# mimic1567heatSink.net
KiCad netlist of a schematic drawn in EAGLE
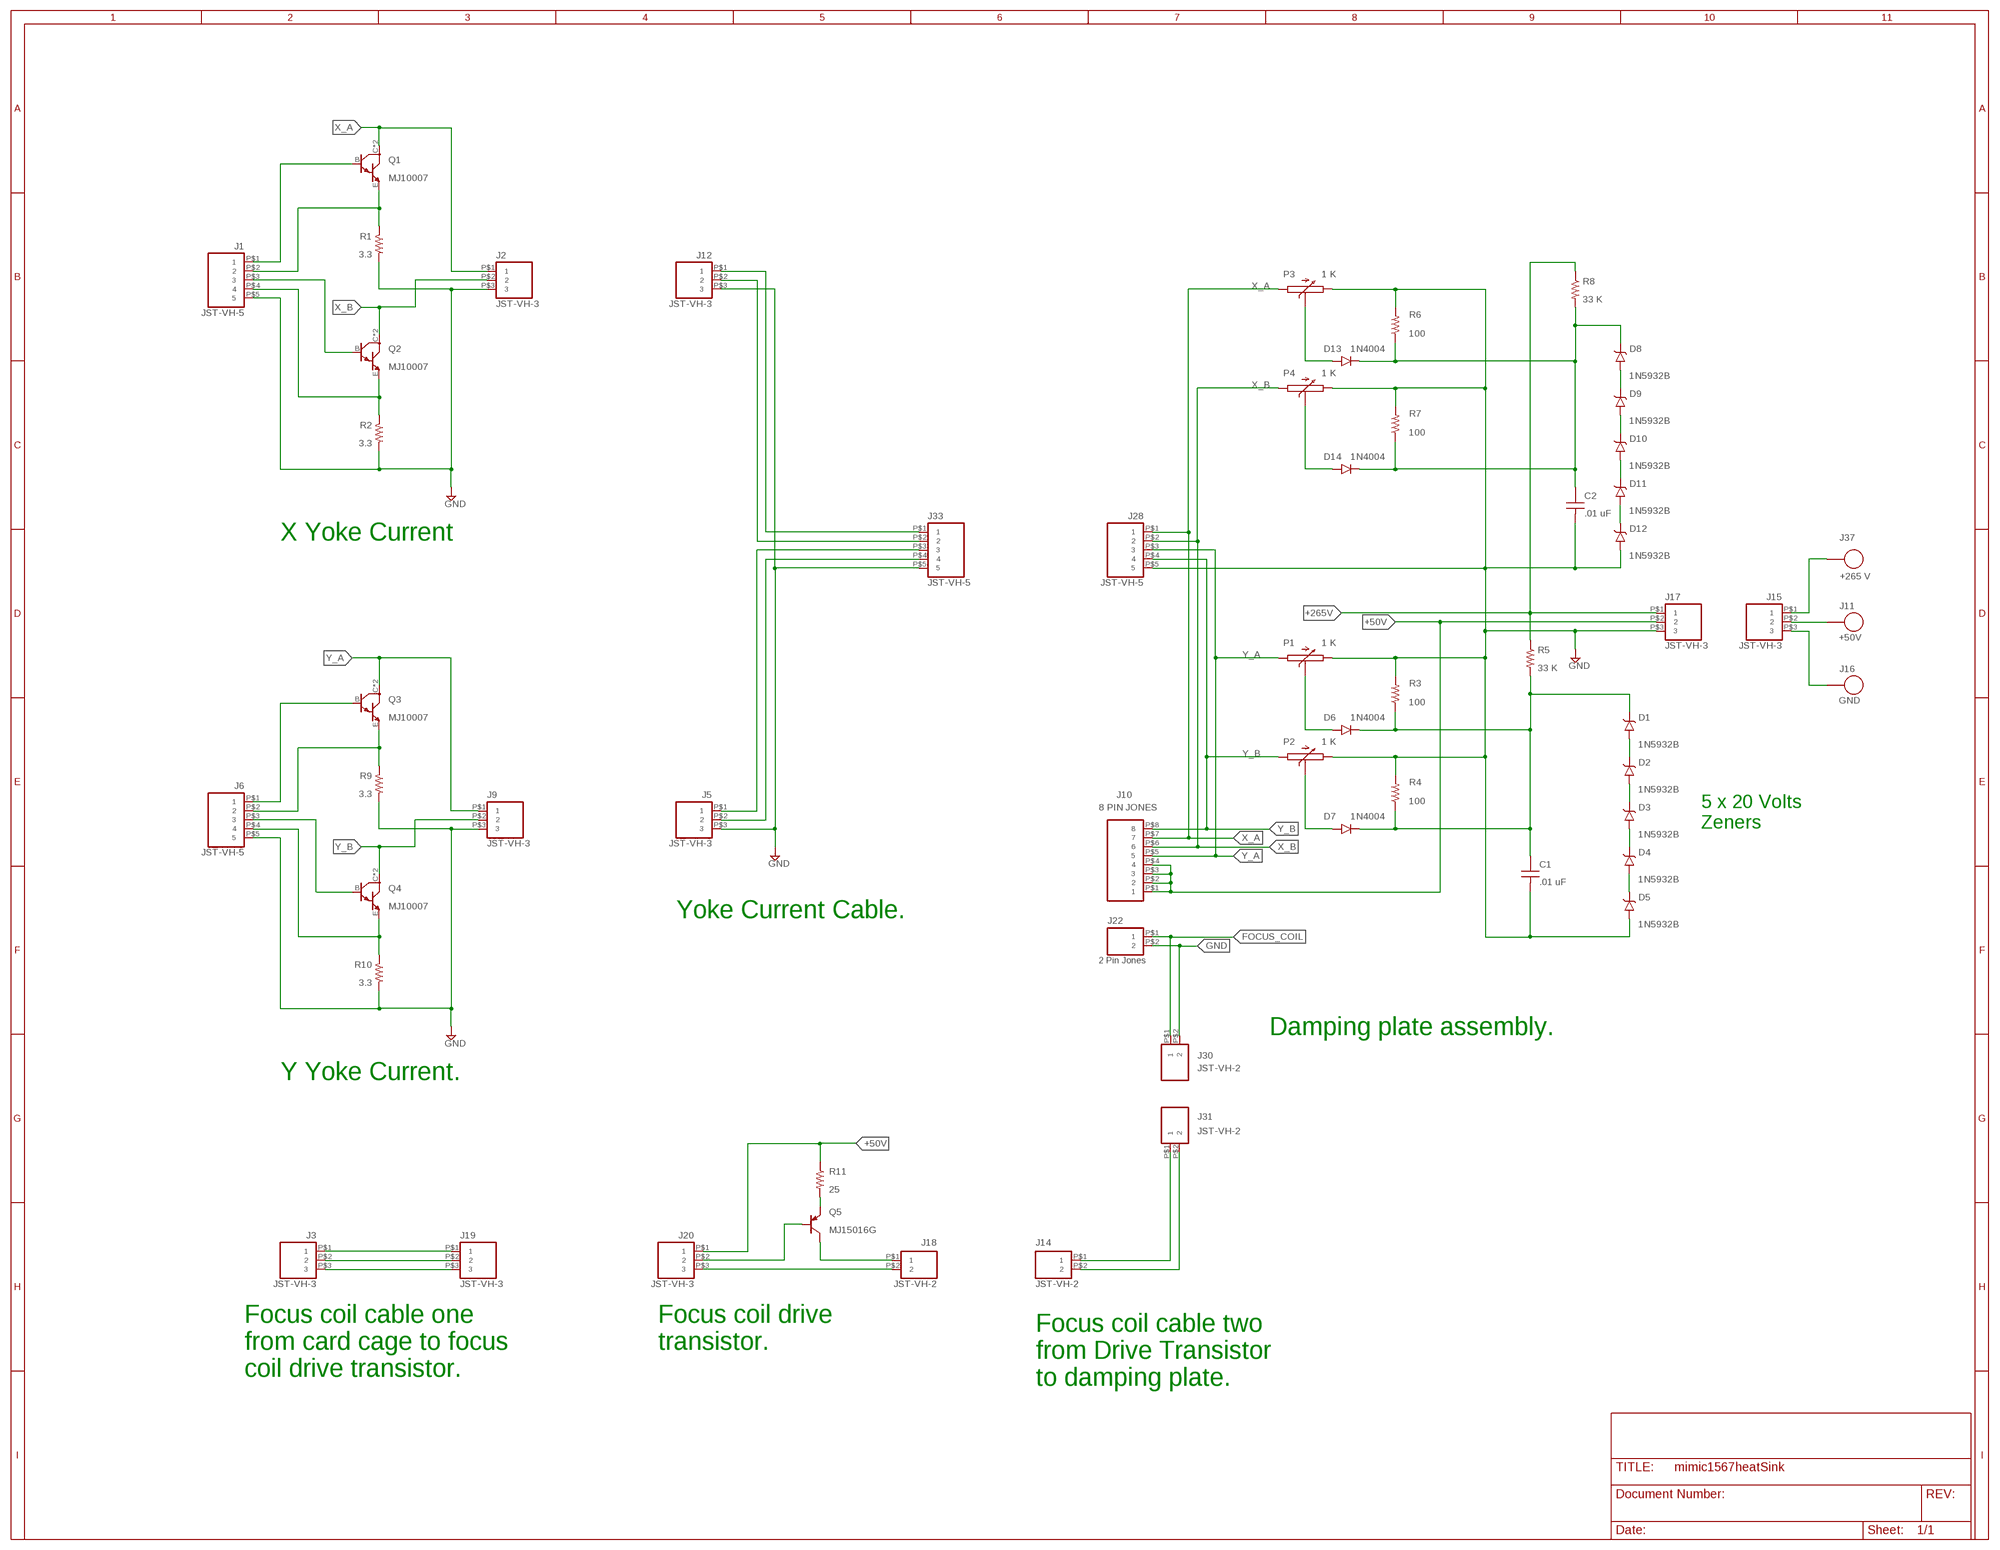
[diagram p0: schematic, sheet 1]

(export (version "E")
  (design (tool "Eeschema 10.0.6"))
  (components
    (comp (ref "C1")
      (value ".01 uF")
      (footprint "eagle-import:CAP_RADIAL_15MM")
      (libsource (lib "eagle-import") (part "FKP1J021004D"))
    )
    (comp (ref "C2")
      (value ".01 uF")
      (footprint "eagle-import:CAP_RADIAL_15MM")
      (libsource (lib "eagle-import") (part "FKP1J021004D"))
    )
    (comp (ref "D1")
      (value "1N5932B")
      (footprint "eagle-import:DO41")
      (libsource (lib "eagle-import") (part "1N5932B"))
    )
    (comp (ref "D2")
      (value "1N5932B")
      (footprint "eagle-import:DO41")
      (libsource (lib "eagle-import") (part "1N5932B"))
    )
    (comp (ref "D3")
      (value "1N5932B")
      (footprint "eagle-import:DO41")
      (libsource (lib "eagle-import") (part "1N5932B"))
    )
    (comp (ref "D4")
      (value "1N5932B")
      (footprint "eagle-import:DO41")
      (libsource (lib "eagle-import") (part "1N5932B"))
    )
    (comp (ref "D5")
      (value "1N5932B")
      (footprint "eagle-import:DO41")
      (libsource (lib "eagle-import") (part "1N5932B"))
    )
    (comp (ref "D6")
      (value "1N4004")
      (footprint "eagle-import:DO-41-10")
      (libsource (lib "eagle-import") (part "1N400X"))
    )
    (comp (ref "D7")
      (value "1N4004")
      (footprint "eagle-import:DO-41-10")
      (libsource (lib "eagle-import") (part "1N400X"))
    )
    (comp (ref "D8")
      (value "1N5932B")
      (footprint "eagle-import:DO41")
      (libsource (lib "eagle-import") (part "1N5932B"))
    )
    (comp (ref "D9")
      (value "1N5932B")
      (footprint "eagle-import:DO41")
      (libsource (lib "eagle-import") (part "1N5932B"))
    )
    (comp (ref "D10")
      (value "1N5932B")
      (footprint "eagle-import:DO41")
      (libsource (lib "eagle-import") (part "1N5932B"))
    )
    (comp (ref "D11")
      (value "1N5932B")
      (footprint "eagle-import:DO41")
      (libsource (lib "eagle-import") (part "1N5932B"))
    )
    (comp (ref "D12")
      (value "1N5932B")
      (footprint "eagle-import:DO41")
      (libsource (lib "eagle-import") (part "1N5932B"))
    )
    (comp (ref "D13")
      (value "1N4004")
      (footprint "eagle-import:DO-41-10")
      (libsource (lib "eagle-import") (part "1N400X"))
    )
    (comp (ref "D14")
      (value "1N4004")
      (footprint "eagle-import:DO-41-10")
      (libsource (lib "eagle-import") (part "1N400X"))
    )
    (comp (ref "J1")
      (value "JST-VH-5")
      (footprint "eagle-import:VHR-5N")
      (libsource (lib "eagle-import") (part "JST-VH-5"))
    )
    (comp (ref "J2")
      (value "JST-VH-3")
      (footprint "eagle-import:VHR-3N")
      (libsource (lib "eagle-import") (part "JST-VH-3"))
    )
    (comp (ref "J3")
      (value "JST-VH-3")
      (footprint "eagle-import:VHR-3N")
      (libsource (lib "eagle-import") (part "JST-VH-3"))
    )
    (comp (ref "J5")
      (value "JST-VH-3")
      (footprint "eagle-import:VHR-3N")
      (libsource (lib "eagle-import") (part "JST-VH-3"))
    )
    (comp (ref "J6")
      (value "JST-VH-5")
      (footprint "eagle-import:VHR-5N")
      (libsource (lib "eagle-import") (part "JST-VH-5"))
    )
    (comp (ref "J9")
      (value "JST-VH-3")
      (footprint "eagle-import:VHR-3N")
      (libsource (lib "eagle-import") (part "JST-VH-3"))
    )
    (comp (ref "J10")
      (value "8 PIN JONES")
      (footprint "eagle-import:8PIN_JONES")
      (libsource (lib "eagle-import") (part "8PIN_JONES_PLUG"))
    )
    (comp (ref "J11")
      (value "+50V")
      (footprint "eagle-import:AWG18")
      (libsource (lib "eagle-import") (part "AWG18"))
    )
    (comp (ref "J12")
      (value "JST-VH-3")
      (footprint "eagle-import:VHR-3N")
      (libsource (lib "eagle-import") (part "JST-VH-3"))
    )
    (comp (ref "J14")
      (value "JST-VH-2")
      (footprint "eagle-import:VHR-2N")
      (libsource (lib "eagle-import") (part "JST-VH-2"))
    )
    (comp (ref "J15")
      (value "JST-VH-3")
      (footprint "eagle-import:VHR-3N")
      (libsource (lib "eagle-import") (part "JST-VH-3"))
    )
    (comp (ref "J16")
      (value "GND")
      (footprint "eagle-import:AWG18")
      (libsource (lib "eagle-import") (part "AWG18"))
    )
    (comp (ref "J17")
      (value "JST-VH-3")
      (footprint "eagle-import:VHR-3N")
      (libsource (lib "eagle-import") (part "JST-VH-3"))
    )
    (comp (ref "J18")
      (value "JST-VH-2")
      (footprint "eagle-import:VHR-2N")
      (libsource (lib "eagle-import") (part "JST-VH-2"))
    )
    (comp (ref "J19")
      (value "JST-VH-3")
      (footprint "eagle-import:VHR-3N")
      (libsource (lib "eagle-import") (part "JST-VH-3"))
    )
    (comp (ref "J20")
      (value "JST-VH-3")
      (footprint "eagle-import:VHR-3N")
      (libsource (lib "eagle-import") (part "JST-VH-3"))
    )
    (comp (ref "J22")
      (value "2 Pin Jones")
      (footprint "eagle-import:2PIN_JONES")
      (libsource (lib "eagle-import") (part "2PIN_JONE_PLUG"))
    )
    (comp (ref "J28")
      (value "JST-VH-5")
      (footprint "eagle-import:VHR-5N")
      (libsource (lib "eagle-import") (part "JST-VH-5"))
    )
    (comp (ref "J30")
      (value "JST-VH-2")
      (footprint "eagle-import:VHR-2N")
      (libsource (lib "eagle-import") (part "JST-VH-2"))
    )
    (comp (ref "J31")
      (value "JST-VH-2")
      (footprint "eagle-import:VHR-2N")
      (libsource (lib "eagle-import") (part "JST-VH-2"))
    )
    (comp (ref "J33")
      (value "JST-VH-5")
      (footprint "eagle-import:VHR-5N")
      (libsource (lib "eagle-import") (part "JST-VH-5"))
    )
    (comp (ref "J37")
      (value "+265 V")
      (footprint "eagle-import:AWG18")
      (libsource (lib "eagle-import") (part "AWG18"))
    )
    (comp (ref "P1")
      (value "1 K")
      (footprint "eagle-import:2W_POT")
      (libsource (lib "eagle-import") (part "2WATT_POT"))
    )
    (comp (ref "P2")
      (value "1 K")
      (footprint "eagle-import:2W_POT")
      (libsource (lib "eagle-import") (part "2WATT_POT"))
    )
    (comp (ref "P3")
      (value "1 K")
      (footprint "eagle-import:2W_POT")
      (libsource (lib "eagle-import") (part "2WATT_POT"))
    )
    (comp (ref "P4")
      (value "1 K")
      (footprint "eagle-import:2W_POT")
      (libsource (lib "eagle-import") (part "2WATT_POT"))
    )
    (comp (ref "Q1")
      (value "MJ10007")
      (footprint "eagle-import:TO3")
      (libsource (lib "eagle-import") (part "MJ10007"))
    )
    (comp (ref "Q2")
      (value "MJ10007")
      (footprint "eagle-import:TO3")
      (libsource (lib "eagle-import") (part "MJ10007"))
    )
    (comp (ref "Q3")
      (value "MJ10007")
      (footprint "eagle-import:TO3")
      (libsource (lib "eagle-import") (part "MJ10007"))
    )
    (comp (ref "Q4")
      (value "MJ10007")
      (footprint "eagle-import:TO3")
      (libsource (lib "eagle-import") (part "MJ10007"))
    )
    (comp (ref "Q5")
      (value "MJ15016G")
      (footprint "eagle-import:TO3")
      (libsource (lib "eagle-import") (part "MJ15016G"))
    )
    (comp (ref "R1")
      (value "3.3")
      (footprint "eagle-import:R_150WATT")
      (libsource (lib "eagle-import") (part "RES3R3150W"))
    )
    (comp (ref "R2")
      (value "3.3")
      (footprint "eagle-import:R_150WATT")
      (libsource (lib "eagle-import") (part "RES3R3150W"))
    )
    (comp (ref "R3")
      (value "100")
      (footprint "eagle-import:0309_12")
      (libsource (lib "eagle-import") (part "R-1/2WATT"))
    )
    (comp (ref "R4")
      (value "100")
      (footprint "eagle-import:0309_12")
      (libsource (lib "eagle-import") (part "R-1/2WATT"))
    )
    (comp (ref "R5")
      (value "33 K")
      (footprint "eagle-import:2WATT_15")
      (libsource (lib "eagle-import") (part "R-2WATT"))
    )
    (comp (ref "R6")
      (value "100")
      (footprint "eagle-import:0309_12")
      (libsource (lib "eagle-import") (part "R-1/2WATT"))
    )
    (comp (ref "R7")
      (value "100")
      (footprint "eagle-import:0309_12")
      (libsource (lib "eagle-import") (part "R-1/2WATT"))
    )
    (comp (ref "R8")
      (value "33 K")
      (footprint "eagle-import:2WATT_15")
      (libsource (lib "eagle-import") (part "R-2WATT"))
    )
    (comp (ref "R9")
      (value "3.3")
      (footprint "eagle-import:R_150WATT")
      (libsource (lib "eagle-import") (part "RES3R3150W"))
    )
    (comp (ref "R10")
      (value "3.3")
      (footprint "eagle-import:R_150WATT")
      (libsource (lib "eagle-import") (part "RES3R3150W"))
    )
    (comp (ref "R11")
      (value "25")
      (footprint "eagle-import:DALE-RH")
      (libsource (lib "eagle-import") (part "RH-25-RESISTOR"))
    )
  )
  (nets
    (net (code "1") (name "+50V") (class "Default")
      (node (ref "J10") (pin "P$1") (pinfunction "1_P$1") (pintype "bidirectional"))
      (node (ref "J10") (pin "P$2") (pinfunction "2_P$2") (pintype "bidirectional"))
      (node (ref "J10") (pin "P$3") (pinfunction "3_P$3") (pintype "bidirectional"))
      (node (ref "J10") (pin "P$4") (pinfunction "4_P$4") (pintype "bidirectional"))
      (node (ref "J17") (pin "P$2") (pinfunction "2_P$2") (pintype "bidirectional"))
      (node (ref "J20") (pin "P$1") (pinfunction "1_P$1") (pintype "bidirectional"))
      (node (ref "R11") (pin "1") (pinfunction "P$1_1") (pintype "passive"))
    )
    (net (code "2") (name "+265V") (class "Default")
      (node (ref "J17") (pin "P$1") (pinfunction "1_P$1") (pintype "bidirectional"))
      (node (ref "R5") (pin "1") (pinfunction "P$1_1") (pintype "passive"))
      (node (ref "R8") (pin "1") (pinfunction "P$1_1") (pintype "passive"))
    )
    (net (code "3") (name "FOCUS_COIL") (class "Default")
      (node (ref "J18") (pin "P$1") (pinfunction "1_P$1") (pintype "bidirectional"))
      (node (ref "J22") (pin "P$1") (pinfunction "1_P$1") (pintype "bidirectional"))
      (node (ref "J30") (pin "P$1") (pinfunction "1_P$1") (pintype "bidirectional"))
      (node (ref "Q5") (pin "C") (pinfunction "C_C") (pintype "passive"))
      (node (ref "Q5") (pin "C/") (pinfunction "C_C/") (pintype "passive"))
    )
    (net (code "4") (name "GND") (class "Default")
      (node (ref "C1") (pin "P$2") (pinfunction "2_P$2") (pintype "passive"))
      (node (ref "C2") (pin "P$2") (pinfunction "2_P$2") (pintype "passive"))
      (node (ref "D12") (pin "A") (pinfunction "A_A") (pintype "passive"))
      (node (ref "D5") (pin "A") (pinfunction "A_A") (pintype "passive"))
      (node (ref "J1") (pin "P$5") (pinfunction "5_P$5") (pintype "bidirectional"))
      (node (ref "J12") (pin "P$3") (pinfunction "3_P$3") (pintype "bidirectional"))
      (node (ref "J17") (pin "P$3") (pinfunction "3_P$3") (pintype "bidirectional"))
      (node (ref "J18") (pin "P$2") (pinfunction "2_P$2") (pintype "bidirectional"))
      (node (ref "J2") (pin "P$3") (pinfunction "3_P$3") (pintype "bidirectional"))
      (node (ref "J20") (pin "P$3") (pinfunction "3_P$3") (pintype "bidirectional"))
      (node (ref "J22") (pin "P$2") (pinfunction "2_P$2") (pintype "bidirectional"))
      (node (ref "J28") (pin "P$5") (pinfunction "5_P$5") (pintype "bidirectional"))
      (node (ref "J30") (pin "P$2") (pinfunction "2_P$2") (pintype "bidirectional"))
      (node (ref "J33") (pin "P$5") (pinfunction "5_P$5") (pintype "bidirectional"))
      (node (ref "J5") (pin "P$3") (pinfunction "3_P$3") (pintype "bidirectional"))
      (node (ref "J6") (pin "P$5") (pinfunction "5_P$5") (pintype "bidirectional"))
      (node (ref "J9") (pin "P$3") (pinfunction "3_P$3") (pintype "bidirectional"))
      (node (ref "P1") (pin "E") (pinfunction "3_E") (pintype "passive"))
      (node (ref "P2") (pin "E") (pinfunction "3_E") (pintype "passive"))
      (node (ref "P3") (pin "E") (pinfunction "3_E") (pintype "passive"))
      (node (ref "P4") (pin "E") (pinfunction "3_E") (pintype "passive"))
      (node (ref "R1") (pin "P$2") (pinfunction "P$2_P$2") (pintype "passive"))
      (node (ref "R10") (pin "P$2") (pinfunction "P$2_P$2") (pintype "passive"))
      (node (ref "R2") (pin "P$2") (pinfunction "P$2_P$2") (pintype "passive"))
      (node (ref "R3") (pin "2") (pinfunction "P$2_2") (pintype "passive"))
      (node (ref "R4") (pin "2") (pinfunction "P$2_2") (pintype "passive"))
      (node (ref "R6") (pin "2") (pinfunction "P$2_2") (pintype "passive"))
      (node (ref "R7") (pin "2") (pinfunction "P$2_2") (pintype "passive"))
      (node (ref "R9") (pin "P$2") (pinfunction "P$2_P$2") (pintype "passive"))
    )
    (net (code "5") (name "Net-(C1-1)") (class "Default")
      (node (ref "C1") (pin "P$1") (pinfunction "1_P$1") (pintype "passive"))
      (node (ref "D1") (pin "C") (pinfunction "C_C") (pintype "passive"))
      (node (ref "D6") (pin "C") (pinfunction "C_C") (pintype "passive"))
      (node (ref "D7") (pin "C") (pinfunction "C_C") (pintype "passive"))
      (node (ref "R3") (pin "1") (pinfunction "P$1_1") (pintype "passive"))
      (node (ref "R4") (pin "1") (pinfunction "P$1_1") (pintype "passive"))
      (node (ref "R5") (pin "2") (pinfunction "P$2_2") (pintype "passive"))
    )
    (net (code "6") (name "Net-(C2-1)") (class "Default")
      (node (ref "C2") (pin "P$1") (pinfunction "1_P$1") (pintype "passive"))
      (node (ref "D13") (pin "C") (pinfunction "C_C") (pintype "passive"))
      (node (ref "D14") (pin "C") (pinfunction "C_C") (pintype "passive"))
      (node (ref "D8") (pin "C") (pinfunction "C_C") (pintype "passive"))
      (node (ref "R6") (pin "1") (pinfunction "P$1_1") (pintype "passive"))
      (node (ref "R7") (pin "1") (pinfunction "P$1_1") (pintype "passive"))
      (node (ref "R8") (pin "2") (pinfunction "P$2_2") (pintype "passive"))
    )
    (net (code "7") (name "Net-(D1-PadA)") (class "Default")
      (node (ref "D1") (pin "A") (pinfunction "A_A") (pintype "passive"))
      (node (ref "D2") (pin "C") (pinfunction "C_C") (pintype "passive"))
    )
    (net (code "8") (name "Net-(D2-PadA)") (class "Default")
      (node (ref "D2") (pin "A") (pinfunction "A_A") (pintype "passive"))
      (node (ref "D3") (pin "C") (pinfunction "C_C") (pintype "passive"))
    )
    (net (code "9") (name "Net-(D3-PadA)") (class "Default")
      (node (ref "D3") (pin "A") (pinfunction "A_A") (pintype "passive"))
      (node (ref "D4") (pin "C") (pinfunction "C_C") (pintype "passive"))
    )
    (net (code "10") (name "Net-(D4-PadA)") (class "Default")
      (node (ref "D4") (pin "A") (pinfunction "A_A") (pintype "passive"))
      (node (ref "D5") (pin "C") (pinfunction "C_C") (pintype "passive"))
    )
    (net (code "11") (name "Net-(D8-PadA)") (class "Default")
      (node (ref "D8") (pin "A") (pinfunction "A_A") (pintype "passive"))
      (node (ref "D9") (pin "C") (pinfunction "C_C") (pintype "passive"))
    )
    (net (code "12") (name "Net-(D10-PadA)") (class "Default")
      (node (ref "D10") (pin "A") (pinfunction "A_A") (pintype "passive"))
      (node (ref "D11") (pin "C") (pinfunction "C_C") (pintype "passive"))
    )
    (net (code "13") (name "Net-(D10-PadC)") (class "Default")
      (node (ref "D10") (pin "C") (pinfunction "C_C") (pintype "passive"))
      (node (ref "D9") (pin "A") (pinfunction "A_A") (pintype "passive"))
    )
    (net (code "14") (name "Net-(D11-PadA)") (class "Default")
      (node (ref "D11") (pin "A") (pinfunction "A_A") (pintype "passive"))
      (node (ref "D12") (pin "C") (pinfunction "C_C") (pintype "passive"))
    )
    (net (code "15") (name "Net-(J1-1)") (class "Default")
      (node (ref "J1") (pin "P$1") (pinfunction "1_P$1") (pintype "bidirectional"))
      (node (ref "Q1") (pin "B") (pinfunction "B_B") (pintype "passive"))
    )
    (net (code "16") (name "Net-(J1-2)") (class "Default")
      (node (ref "J1") (pin "P$2") (pinfunction "2_P$2") (pintype "bidirectional"))
      (node (ref "Q1") (pin "E") (pinfunction "E_E") (pintype "passive"))
      (node (ref "R1") (pin "P$1") (pinfunction "P$1_P$1") (pintype "passive"))
    )
    (net (code "17") (name "Net-(J1-3)") (class "Default")
      (node (ref "J1") (pin "P$3") (pinfunction "3_P$3") (pintype "bidirectional"))
      (node (ref "Q2") (pin "B") (pinfunction "B_B") (pintype "passive"))
    )
    (net (code "18") (name "Net-(J1-4)") (class "Default")
      (node (ref "J1") (pin "P$4") (pinfunction "4_P$4") (pintype "bidirectional"))
      (node (ref "Q2") (pin "E") (pinfunction "E_E") (pintype "passive"))
      (node (ref "R2") (pin "P$1") (pinfunction "P$1_P$1") (pintype "passive"))
    )
    (net (code "19") (name "Net-(J6-1)") (class "Default")
      (node (ref "J6") (pin "P$1") (pinfunction "1_P$1") (pintype "bidirectional"))
      (node (ref "Q3") (pin "B") (pinfunction "B_B") (pintype "passive"))
    )
    (net (code "20") (name "Net-(J6-2)") (class "Default")
      (node (ref "J6") (pin "P$2") (pinfunction "2_P$2") (pintype "bidirectional"))
      (node (ref "Q3") (pin "E") (pinfunction "E_E") (pintype "passive"))
      (node (ref "R9") (pin "P$1") (pinfunction "P$1_P$1") (pintype "passive"))
    )
    (net (code "21") (name "Net-(J6-3)") (class "Default")
      (node (ref "J6") (pin "P$3") (pinfunction "3_P$3") (pintype "bidirectional"))
      (node (ref "Q4") (pin "B") (pinfunction "B_B") (pintype "passive"))
    )
    (net (code "22") (name "Net-(J6-4)") (class "Default")
      (node (ref "J6") (pin "P$4") (pinfunction "4_P$4") (pintype "bidirectional"))
      (node (ref "Q4") (pin "E") (pinfunction "E_E") (pintype "passive"))
      (node (ref "R10") (pin "P$1") (pinfunction "P$1_P$1") (pintype "passive"))
    )
    (net (code "23") (name "Net-(J14-1)") (class "Default")
      (node (ref "J14") (pin "P$1") (pinfunction "1_P$1") (pintype "bidirectional"))
      (node (ref "J31") (pin "P$1") (pinfunction "1_P$1") (pintype "bidirectional"))
    )
    (net (code "24") (name "Net-(J14-2)") (class "Default")
      (node (ref "J14") (pin "P$2") (pinfunction "2_P$2") (pintype "bidirectional"))
      (node (ref "J31") (pin "P$2") (pinfunction "2_P$2") (pintype "bidirectional"))
    )
    (net (code "25") (name "Net-(J15-1)") (class "Default")
      (node (ref "J15") (pin "P$1") (pinfunction "1_P$1") (pintype "bidirectional"))
      (node (ref "J37") (pin "P$1") (pinfunction "P$1_P$1") (pintype "bidirectional"))
    )
    (net (code "26") (name "Net-(J15-2)") (class "Default")
      (node (ref "J11") (pin "P$1") (pinfunction "P$1_P$1") (pintype "bidirectional"))
      (node (ref "J15") (pin "P$2") (pinfunction "2_P$2") (pintype "bidirectional"))
    )
    (net (code "27") (name "Net-(J15-3)") (class "Default")
      (node (ref "J15") (pin "P$3") (pinfunction "3_P$3") (pintype "bidirectional"))
      (node (ref "J16") (pin "P$1") (pinfunction "P$1_P$1") (pintype "bidirectional"))
    )
    (net (code "28") (name "Net-(J19-1)") (class "Default")
      (node (ref "J19") (pin "P$1") (pinfunction "1_P$1") (pintype "bidirectional"))
      (node (ref "J3") (pin "P$1") (pinfunction "1_P$1") (pintype "bidirectional"))
    )
    (net (code "29") (name "Net-(J19-2)") (class "Default")
      (node (ref "J19") (pin "P$2") (pinfunction "2_P$2") (pintype "bidirectional"))
      (node (ref "J3") (pin "P$2") (pinfunction "2_P$2") (pintype "bidirectional"))
    )
    (net (code "30") (name "Net-(J19-3)") (class "Default")
      (node (ref "J19") (pin "P$3") (pinfunction "3_P$3") (pintype "bidirectional"))
      (node (ref "J3") (pin "P$3") (pinfunction "3_P$3") (pintype "bidirectional"))
    )
    (net (code "31") (name "Net-(J20-2)") (class "Default")
      (node (ref "J20") (pin "P$2") (pinfunction "2_P$2") (pintype "bidirectional"))
      (node (ref "Q5") (pin "B") (pinfunction "B_B") (pintype "passive"))
    )
    (net (code "32") (name "Net-(P1-2)") (class "Default")
      (node (ref "D6") (pin "A") (pinfunction "A_A") (pintype "passive"))
      (node (ref "P1") (pin "S") (pinfunction "2_S") (pintype "passive"))
    )
    (net (code "33") (name "Net-(P2-2)") (class "Default")
      (node (ref "D7") (pin "A") (pinfunction "A_A") (pintype "passive"))
      (node (ref "P2") (pin "S") (pinfunction "2_S") (pintype "passive"))
    )
    (net (code "34") (name "Net-(P3-2)") (class "Default")
      (node (ref "D13") (pin "A") (pinfunction "A_A") (pintype "passive"))
      (node (ref "P3") (pin "S") (pinfunction "2_S") (pintype "passive"))
    )
    (net (code "35") (name "Net-(P4-2)") (class "Default")
      (node (ref "D14") (pin "A") (pinfunction "A_A") (pintype "passive"))
      (node (ref "P4") (pin "S") (pinfunction "2_S") (pintype "passive"))
    )
    (net (code "36") (name "Net-(R11-P$2)") (class "Default")
      (node (ref "Q5") (pin "E") (pinfunction "E_E") (pintype "passive"))
      (node (ref "R11") (pin "2") (pinfunction "P$2_2") (pintype "passive"))
    )
    (net (code "37") (name "X_A") (class "Default")
      (node (ref "J10") (pin "P$7") (pinfunction "7_P$7") (pintype "bidirectional"))
      (node (ref "J12") (pin "P$1") (pinfunction "1_P$1") (pintype "bidirectional"))
      (node (ref "J2") (pin "P$1") (pinfunction "1_P$1") (pintype "bidirectional"))
      (node (ref "J28") (pin "P$1") (pinfunction "1_P$1") (pintype "bidirectional"))
      (node (ref "J33") (pin "P$1") (pinfunction "1_P$1") (pintype "bidirectional"))
      (node (ref "P3") (pin "A") (pinfunction "1_A") (pintype "passive"))
      (node (ref "Q1") (pin "C") (pinfunction "C_C") (pintype "passive"))
      (node (ref "Q1") (pin "C/") (pinfunction "C_C/") (pintype "passive"))
    )
    (net (code "38") (name "X_B") (class "Default")
      (node (ref "J10") (pin "P$6") (pinfunction "6_P$6") (pintype "bidirectional"))
      (node (ref "J12") (pin "P$2") (pinfunction "2_P$2") (pintype "bidirectional"))
      (node (ref "J2") (pin "P$2") (pinfunction "2_P$2") (pintype "bidirectional"))
      (node (ref "J28") (pin "P$2") (pinfunction "2_P$2") (pintype "bidirectional"))
      (node (ref "J33") (pin "P$2") (pinfunction "2_P$2") (pintype "bidirectional"))
      (node (ref "P4") (pin "A") (pinfunction "1_A") (pintype "passive"))
      (node (ref "Q2") (pin "C") (pinfunction "C_C") (pintype "passive"))
      (node (ref "Q2") (pin "C/") (pinfunction "C_C/") (pintype "passive"))
    )
    (net (code "39") (name "Y_A") (class "Default")
      (node (ref "J10") (pin "P$5") (pinfunction "5_P$5") (pintype "bidirectional"))
      (node (ref "J28") (pin "P$3") (pinfunction "3_P$3") (pintype "bidirectional"))
      (node (ref "J33") (pin "P$3") (pinfunction "3_P$3") (pintype "bidirectional"))
      (node (ref "J5") (pin "P$1") (pinfunction "1_P$1") (pintype "bidirectional"))
      (node (ref "J9") (pin "P$1") (pinfunction "1_P$1") (pintype "bidirectional"))
      (node (ref "P1") (pin "A") (pinfunction "1_A") (pintype "passive"))
      (node (ref "Q3") (pin "C") (pinfunction "C_C") (pintype "passive"))
      (node (ref "Q3") (pin "C/") (pinfunction "C_C/") (pintype "passive"))
    )
    (net (code "40") (name "Y_B") (class "Default")
      (node (ref "J10") (pin "P$8") (pinfunction "8_P$8") (pintype "bidirectional"))
      (node (ref "J28") (pin "P$4") (pinfunction "4_P$4") (pintype "bidirectional"))
      (node (ref "J33") (pin "P$4") (pinfunction "4_P$4") (pintype "bidirectional"))
      (node (ref "J5") (pin "P$2") (pinfunction "2_P$2") (pintype "bidirectional"))
      (node (ref "J9") (pin "P$2") (pinfunction "2_P$2") (pintype "bidirectional"))
      (node (ref "P2") (pin "A") (pinfunction "1_A") (pintype "passive"))
      (node (ref "Q4") (pin "C") (pinfunction "C_C") (pintype "passive"))
      (node (ref "Q4") (pin "C/") (pinfunction "C_C/") (pintype "passive"))
    )
  )
)
